# MonsterMoto-Shield-v12.net
KiCad netlist of a schematic drawn in EAGLE
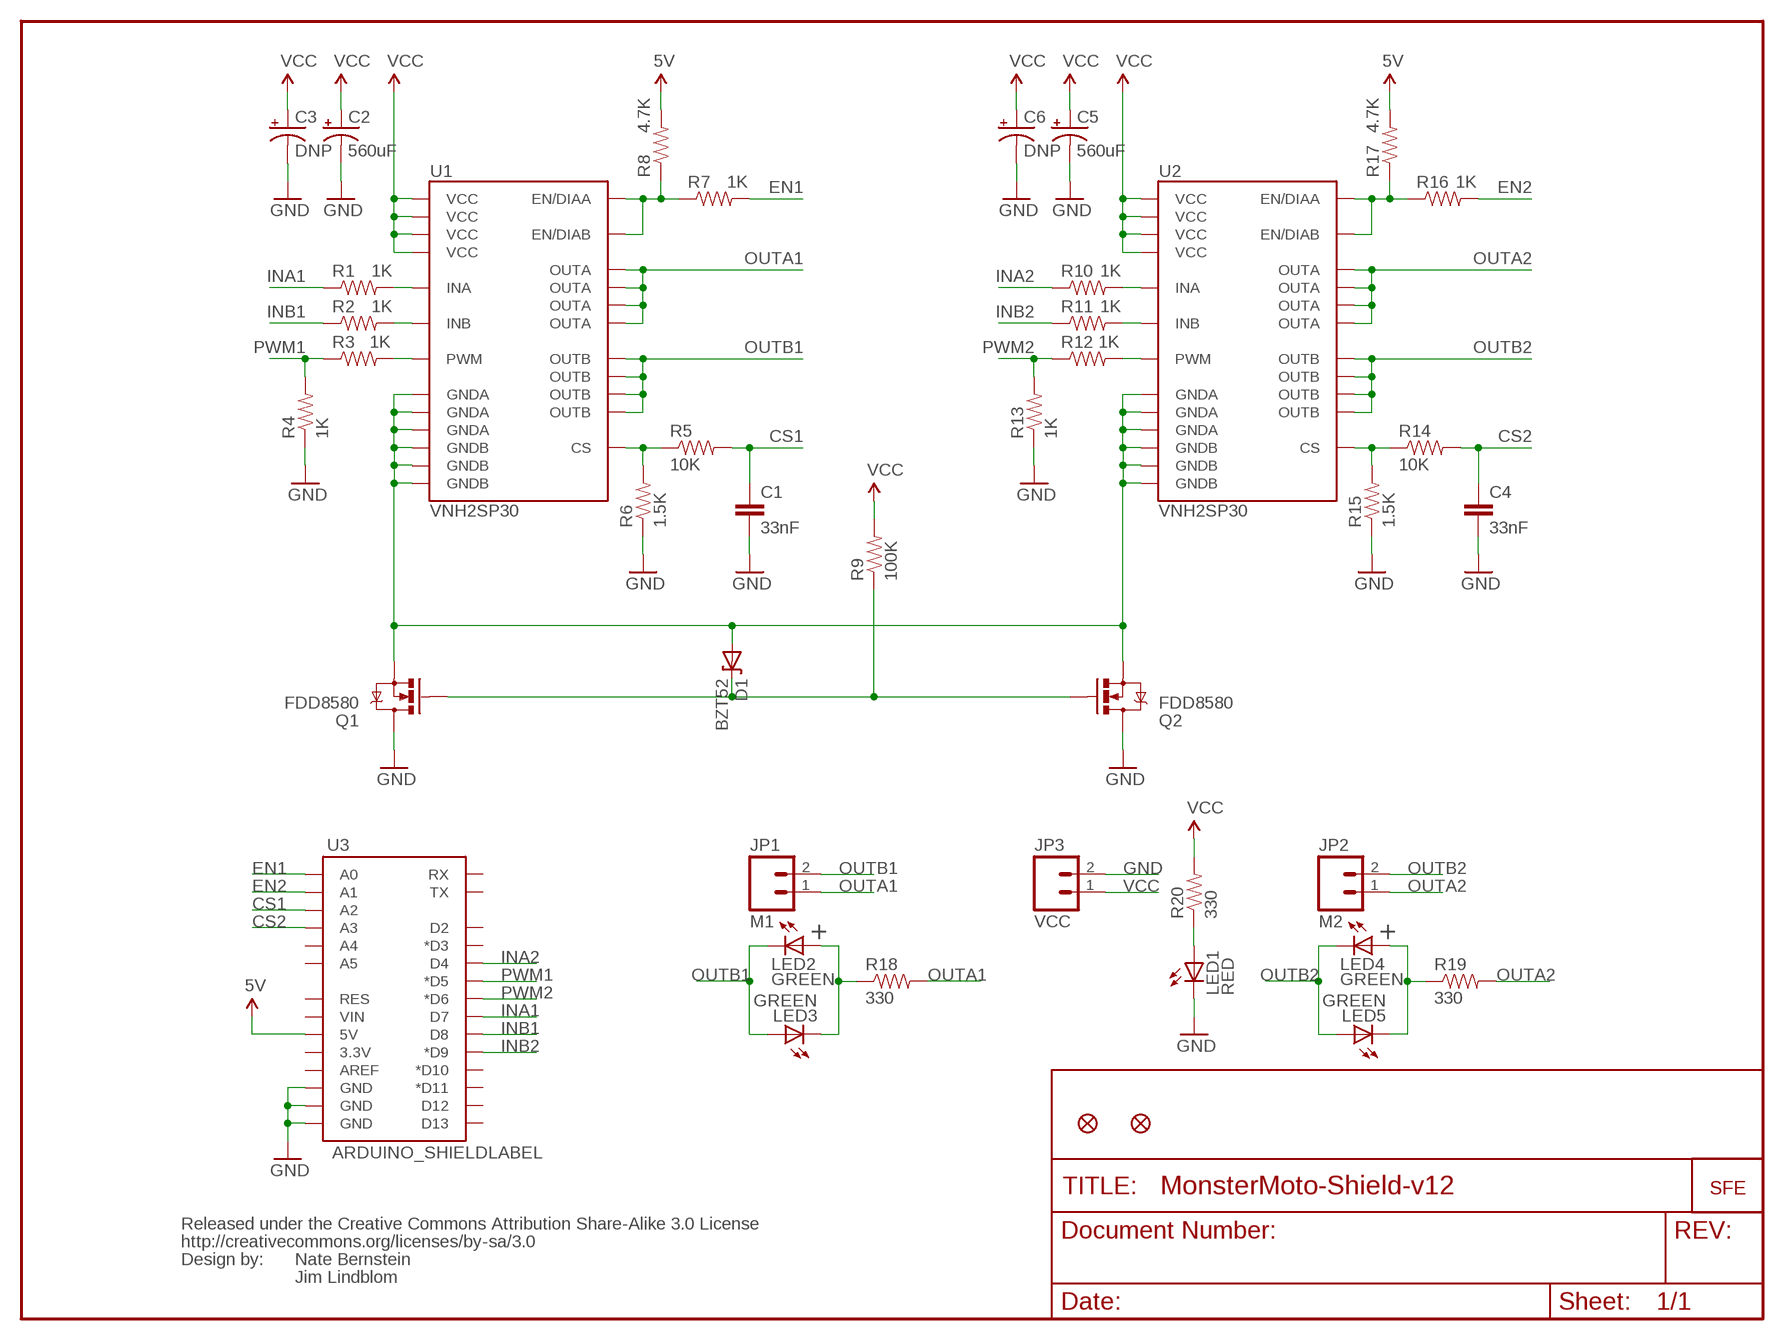
[diagram p0: schematic, sheet 1]

(export (version "E")
  (design (tool "Eeschema 10.0.6"))
  (components
    (comp (ref "C1")
      (value "33nF")
      (footprint "eagle-import:0402-CAP")
      (libsource (lib "eagle-import") (part "CAP0402-CAP"))
    )
    (comp (ref "C2")
      (value "560uF")
      (footprint "eagle-import:PANASONIC_G")
      (libsource (lib "eagle-import") (part "CAP_POLG"))
    )
    (comp (ref "C3")
      (value "DNP")
      (footprint "eagle-import:CPOL-RADIAL-1000UF-25V")
      (libsource (lib "eagle-import") (part "CAP_POLPTH4"))
    )
    (comp (ref "C4")
      (value "33nF")
      (footprint "eagle-import:0402-CAP")
      (libsource (lib "eagle-import") (part "CAP0402-CAP"))
    )
    (comp (ref "C5")
      (value "560uF")
      (footprint "eagle-import:PANASONIC_G")
      (libsource (lib "eagle-import") (part "CAP_POLG"))
    )
    (comp (ref "C6")
      (value "DNP")
      (footprint "eagle-import:CPOL-RADIAL-1000UF-25V")
      (libsource (lib "eagle-import") (part "CAP_POLPTH4"))
    )
    (comp (ref "D1")
      (value "BZT52")
      (footprint "eagle-import:SOD-323")
      (libsource (lib "eagle-import") (part "DIODE-ZENER-BZT52"))
    )
    (comp (ref "JP1")
      (value "M1")
      (footprint "eagle-import:1X02_XTRA_BIG")
      (libsource (lib "eagle-import") (part "M02PTH4"))
    )
    (comp (ref "JP2")
      (value "M2")
      (footprint "eagle-import:1X02_XTRA_BIG")
      (libsource (lib "eagle-import") (part "M02PTH4"))
    )
    (comp (ref "JP3")
      (value "VCC")
      (footprint "eagle-import:1X02_XTRA_BIG")
      (libsource (lib "eagle-import") (part "M02PTH4"))
    )
    (comp (ref "JP4")
      (value "FIDUCIAL1X2")
      (footprint "eagle-import:FIDUCIAL-1X2")
      (libsource (lib "eagle-import") (part "FIDUCIAL1X2"))
    )
    (comp (ref "JP5")
      (value "LOGO-SFENEW")
      (footprint "eagle-import:SFE-NEW-WEBLOGO")
      (libsource (lib "eagle-import") (part "LOGO-SFENEW"))
    )
    (comp (ref "JP6")
      (value "FIDUCIAL1X2")
      (footprint "eagle-import:FIDUCIAL-1X2")
      (libsource (lib "eagle-import") (part "FIDUCIAL1X2"))
    )
    (comp (ref "LED1")
      (value "RED")
      (footprint "eagle-import:LED-0603")
      (libsource (lib "eagle-import") (part "LED0603"))
    )
    (comp (ref "LED2")
      (value "GREEN")
      (footprint "eagle-import:LED-0603")
      (libsource (lib "eagle-import") (part "LED0603"))
    )
    (comp (ref "LED3")
      (value "GREEN")
      (footprint "eagle-import:LED-0603")
      (libsource (lib "eagle-import") (part "LED0603"))
    )
    (comp (ref "LED4")
      (value "GREEN")
      (footprint "eagle-import:LED-0603")
      (libsource (lib "eagle-import") (part "LED0603"))
    )
    (comp (ref "LED5")
      (value "GREEN")
      (footprint "eagle-import:LED-0603")
      (libsource (lib "eagle-import") (part "LED0603"))
    )
    (comp (ref "Q1")
      (value "FDD8580")
      (footprint "eagle-import:DPAK")
      (libsource (lib "eagle-import") (part "MOSFET-NCHANNELFDD8580"))
    )
    (comp (ref "Q2")
      (value "FDD8580")
      (footprint "eagle-import:DPAK")
      (libsource (lib "eagle-import") (part "MOSFET-NCHANNELFDD8580"))
    )
    (comp (ref "R1")
      (value "1K")
      (footprint "eagle-import:0402-RES")
      (libsource (lib "eagle-import") (part "RESISTOR0402-RES"))
    )
    (comp (ref "R2")
      (value "1K")
      (footprint "eagle-import:0402-RES")
      (libsource (lib "eagle-import") (part "RESISTOR0402-RES"))
    )
    (comp (ref "R3")
      (value "1K")
      (footprint "eagle-import:0402-RES")
      (libsource (lib "eagle-import") (part "RESISTOR0402-RES"))
    )
    (comp (ref "R4")
      (value "1K")
      (footprint "eagle-import:0402-RES")
      (libsource (lib "eagle-import") (part "RESISTOR0402-RES"))
    )
    (comp (ref "R5")
      (value "10K")
      (footprint "eagle-import:0402-RES")
      (libsource (lib "eagle-import") (part "RESISTOR0402-RES"))
    )
    (comp (ref "R6")
      (value "1.5K")
      (footprint "eagle-import:0402-RES")
      (libsource (lib "eagle-import") (part "RESISTOR0402-RES"))
    )
    (comp (ref "R7")
      (value "1K")
      (footprint "eagle-import:0402-RES")
      (libsource (lib "eagle-import") (part "RESISTOR0402-RES"))
    )
    (comp (ref "R8")
      (value "4.7K")
      (footprint "eagle-import:0402-RES")
      (libsource (lib "eagle-import") (part "RESISTOR0402-RES"))
    )
    (comp (ref "R9")
      (value "100K")
      (footprint "eagle-import:0402-RES")
      (libsource (lib "eagle-import") (part "RESISTOR0402-RES"))
    )
    (comp (ref "R10")
      (value "1K")
      (footprint "eagle-import:0402-RES")
      (libsource (lib "eagle-import") (part "RESISTOR0402-RES"))
    )
    (comp (ref "R11")
      (value "1K")
      (footprint "eagle-import:0402-RES")
      (libsource (lib "eagle-import") (part "RESISTOR0402-RES"))
    )
    (comp (ref "R12")
      (value "1K")
      (footprint "eagle-import:0402-RES")
      (libsource (lib "eagle-import") (part "RESISTOR0402-RES"))
    )
    (comp (ref "R13")
      (value "1K")
      (footprint "eagle-import:0402-RES")
      (libsource (lib "eagle-import") (part "RESISTOR0402-RES"))
    )
    (comp (ref "R14")
      (value "10K")
      (footprint "eagle-import:0402-RES")
      (libsource (lib "eagle-import") (part "RESISTOR0402-RES"))
    )
    (comp (ref "R15")
      (value "1.5K")
      (footprint "eagle-import:0402-RES")
      (libsource (lib "eagle-import") (part "RESISTOR0402-RES"))
    )
    (comp (ref "R16")
      (value "1K")
      (footprint "eagle-import:0402-RES")
      (libsource (lib "eagle-import") (part "RESISTOR0402-RES"))
    )
    (comp (ref "R17")
      (value "4.7K")
      (footprint "eagle-import:0402-RES")
      (libsource (lib "eagle-import") (part "RESISTOR0402-RES"))
    )
    (comp (ref "R18")
      (value "330")
      (footprint "eagle-import:0402-RES")
      (libsource (lib "eagle-import") (part "RESISTOR0402-RES"))
    )
    (comp (ref "R19")
      (value "330")
      (footprint "eagle-import:0402-RES")
      (libsource (lib "eagle-import") (part "RESISTOR0402-RES"))
    )
    (comp (ref "R20")
      (value "330")
      (footprint "eagle-import:0402-RES")
      (libsource (lib "eagle-import") (part "RESISTOR0402-RES"))
    )
    (comp (ref "U$6")
      (value "CREATIVE_COMMONS")
      (footprint "eagle-import:CREATIVE_COMMONS")
      (libsource (lib "eagle-import") (part "CREATIVE_COMMONS"))
    )
    (comp (ref "U1")
      (value "VNH2SP30")
      (footprint "eagle-import:VNH2SP30")
      (libsource (lib "eagle-import") (part "VNH2SP30"))
    )
    (comp (ref "U2")
      (value "VNH2SP30")
      (footprint "eagle-import:VNH2SP30")
      (libsource (lib "eagle-import") (part "VNH2SP30"))
    )
    (comp (ref "U3")
      (value "ARDUINO_SHIELDLABEL")
      (footprint "eagle-import:DUEMILANOVE_SHIELD")
      (libsource (lib "eagle-import") (part "ARDUINO_SHIELDLABEL"))
    )
  )
  (nets
    (net (code "1") (name "/CS1") (class "Default")
      (node (ref "C1") (pin "1") (pinfunction "1_1") (pintype "passive"))
      (node (ref "R5") (pin "2") (pinfunction "2_2") (pintype "passive"))
      (node (ref "U3") (pin "A2") (pinfunction "A2_A2") (pintype "bidirectional"))
    )
    (net (code "2") (name "/CS2") (class "Default")
      (node (ref "C4") (pin "1") (pinfunction "1_1") (pintype "passive"))
      (node (ref "R14") (pin "2") (pinfunction "2_2") (pintype "passive"))
      (node (ref "U3") (pin "A3") (pinfunction "A3_A3") (pintype "bidirectional"))
    )
    (net (code "3") (name "/EN1") (class "Default")
      (node (ref "R7") (pin "2") (pinfunction "2_2") (pintype "passive"))
      (node (ref "U3") (pin "A0") (pinfunction "A0_A0") (pintype "bidirectional"))
    )
    (net (code "4") (name "/EN2") (class "Default")
      (node (ref "R16") (pin "2") (pinfunction "2_2") (pintype "passive"))
      (node (ref "U3") (pin "A1") (pinfunction "A1_A1") (pintype "bidirectional"))
    )
    (net (code "5") (name "/INA1") (class "Default")
      (node (ref "R1") (pin "1") (pinfunction "1_1") (pintype "passive"))
      (node (ref "U3") (pin "D7") (pinfunction "D7_D7") (pintype "bidirectional"))
    )
    (net (code "6") (name "/INA2") (class "Default")
      (node (ref "R10") (pin "1") (pinfunction "1_1") (pintype "passive"))
      (node (ref "U3") (pin "D4") (pinfunction "D4_D4") (pintype "bidirectional"))
    )
    (net (code "7") (name "/INB1") (class "Default")
      (node (ref "R2") (pin "1") (pinfunction "1_1") (pintype "passive"))
      (node (ref "U3") (pin "D8") (pinfunction "D8_D8") (pintype "bidirectional"))
    )
    (net (code "8") (name "/INB2") (class "Default")
      (node (ref "R11") (pin "1") (pinfunction "1_1") (pintype "passive"))
      (node (ref "U3") (pin "D9") (pinfunction "*D9_D9") (pintype "bidirectional"))
    )
    (net (code "9") (name "/OUTA1") (class "Default")
      (node (ref "JP1") (pin "1") (pinfunction "1_1") (pintype "passive"))
      (node (ref "R18") (pin "2") (pinfunction "2_2") (pintype "passive"))
      (node (ref "U1") (pin "1") (pinfunction "OUTA_1") (pintype "bidirectional"))
      (node (ref "U1") (pin "25") (pinfunction "OUTA_25") (pintype "bidirectional"))
      (node (ref "U1") (pin "30") (pinfunction "OUTA_30") (pintype "bidirectional"))
      (node (ref "U1") (pin "SLUG3") (pinfunction "OUTA_SLUG3") (pintype "bidirectional"))
    )
    (net (code "10") (name "/OUTA2") (class "Default")
      (node (ref "JP2") (pin "1") (pinfunction "1_1") (pintype "passive"))
      (node (ref "R19") (pin "2") (pinfunction "2_2") (pintype "passive"))
      (node (ref "U2") (pin "1") (pinfunction "OUTA_1") (pintype "bidirectional"))
      (node (ref "U2") (pin "25") (pinfunction "OUTA_25") (pintype "bidirectional"))
      (node (ref "U2") (pin "30") (pinfunction "OUTA_30") (pintype "bidirectional"))
      (node (ref "U2") (pin "SLUG3") (pinfunction "OUTA_SLUG3") (pintype "bidirectional"))
    )
    (net (code "11") (name "/OUTB1") (class "Default")
      (node (ref "JP1") (pin "2") (pinfunction "2_2") (pintype "passive"))
      (node (ref "LED2") (pin "C") (pinfunction "C_C") (pintype "passive"))
      (node (ref "LED3") (pin "A") (pinfunction "A_A") (pintype "passive"))
      (node (ref "U1") (pin "15") (pinfunction "OUTB_15") (pintype "bidirectional"))
      (node (ref "U1") (pin "16") (pinfunction "OUTB_16") (pintype "bidirectional"))
      (node (ref "U1") (pin "21") (pinfunction "OUTB_21") (pintype "bidirectional"))
      (node (ref "U1") (pin "SLUG2") (pinfunction "OUTB_SLUG2") (pintype "bidirectional"))
    )
    (net (code "12") (name "/OUTB2") (class "Default")
      (node (ref "JP2") (pin "2") (pinfunction "2_2") (pintype "passive"))
      (node (ref "LED4") (pin "C") (pinfunction "C_C") (pintype "passive"))
      (node (ref "LED5") (pin "A") (pinfunction "A_A") (pintype "passive"))
      (node (ref "U2") (pin "15") (pinfunction "OUTB_15") (pintype "bidirectional"))
      (node (ref "U2") (pin "16") (pinfunction "OUTB_16") (pintype "bidirectional"))
      (node (ref "U2") (pin "21") (pinfunction "OUTB_21") (pintype "bidirectional"))
      (node (ref "U2") (pin "SLUG2") (pinfunction "OUTB_SLUG2") (pintype "bidirectional"))
    )
    (net (code "13") (name "/PWM1") (class "Default")
      (node (ref "R3") (pin "1") (pinfunction "1_1") (pintype "passive"))
      (node (ref "R4") (pin "2") (pinfunction "2_2") (pintype "passive"))
      (node (ref "U3") (pin "D5") (pinfunction "*D5_D5") (pintype "bidirectional"))
    )
    (net (code "14") (name "/PWM2") (class "Default")
      (node (ref "R12") (pin "1") (pinfunction "1_1") (pintype "passive"))
      (node (ref "R13") (pin "2") (pinfunction "2_2") (pintype "passive"))
      (node (ref "U3") (pin "D6") (pinfunction "*D6_D6") (pintype "bidirectional"))
    )
    (net (code "15") (name "5V") (class "Default")
      (node (ref "R17") (pin "2") (pinfunction "2_2") (pintype "passive"))
      (node (ref "R8") (pin "2") (pinfunction "2_2") (pintype "passive"))
      (node (ref "U3") (pin "5V") (pinfunction "5V_5V") (pintype "bidirectional"))
    )
    (net (code "16") (name "GND") (class "Default")
      (node (ref "C1") (pin "2") (pinfunction "2_2") (pintype "passive"))
      (node (ref "C2") (pin "-") (pinfunction "-_-") (pintype "passive"))
      (node (ref "C3") (pin "2") (pinfunction "-_2") (pintype "passive"))
      (node (ref "C4") (pin "2") (pinfunction "2_2") (pintype "passive"))
      (node (ref "C5") (pin "-") (pinfunction "-_-") (pintype "passive"))
      (node (ref "C6") (pin "2") (pinfunction "-_2") (pintype "passive"))
      (node (ref "JP3") (pin "2") (pinfunction "2_2") (pintype "passive"))
      (node (ref "LED1") (pin "C") (pinfunction "C_C") (pintype "passive"))
      (node (ref "Q1") (pin "4") (pinfunction "D_4") (pintype "passive"))
      (node (ref "Q2") (pin "4") (pinfunction "D_4") (pintype "passive"))
      (node (ref "R13") (pin "1") (pinfunction "1_1") (pintype "passive"))
      (node (ref "R15") (pin "1") (pinfunction "1_1") (pintype "passive"))
      (node (ref "R4") (pin "1") (pinfunction "1_1") (pintype "passive"))
      (node (ref "R6") (pin "1") (pinfunction "1_1") (pintype "passive"))
      (node (ref "U3") (pin "GND@0") (pinfunction "GND_GND@0") (pintype "bidirectional"))
      (node (ref "U3") (pin "GND@1") (pinfunction "GND_GND@1") (pintype "bidirectional"))
      (node (ref "U3") (pin "GND@2") (pinfunction "GND_GND@2") (pintype "bidirectional"))
    )
    (net (code "17") (name "Net-(D1-A)") (class "Default")
      (node (ref "D1") (pin "2") (pinfunction "A_2") (pintype "passive"))
      (node (ref "Q1") (pin "3") (pinfunction "S_3") (pintype "passive"))
      (node (ref "Q2") (pin "3") (pinfunction "S_3") (pintype "passive"))
      (node (ref "U1") (pin "18") (pinfunction "GNDB_18") (pintype "bidirectional"))
      (node (ref "U1") (pin "19") (pinfunction "GNDB_19") (pintype "bidirectional"))
      (node (ref "U1") (pin "20") (pinfunction "GNDB_20") (pintype "bidirectional"))
      (node (ref "U1") (pin "26") (pinfunction "GNDA_26") (pintype "bidirectional"))
      (node (ref "U1") (pin "27") (pinfunction "GNDA_27") (pintype "bidirectional"))
      (node (ref "U1") (pin "28") (pinfunction "GNDA_28") (pintype "bidirectional"))
      (node (ref "U2") (pin "18") (pinfunction "GNDB_18") (pintype "bidirectional"))
      (node (ref "U2") (pin "19") (pinfunction "GNDB_19") (pintype "bidirectional"))
      (node (ref "U2") (pin "20") (pinfunction "GNDB_20") (pintype "bidirectional"))
      (node (ref "U2") (pin "26") (pinfunction "GNDA_26") (pintype "bidirectional"))
      (node (ref "U2") (pin "27") (pinfunction "GNDA_27") (pintype "bidirectional"))
      (node (ref "U2") (pin "28") (pinfunction "GNDA_28") (pintype "bidirectional"))
    )
    (net (code "18") (name "Net-(D1-C)") (class "Default")
      (node (ref "D1") (pin "1") (pinfunction "C_1") (pintype "passive"))
      (node (ref "Q1") (pin "1") (pinfunction "G_1") (pintype "passive"))
      (node (ref "Q2") (pin "1") (pinfunction "G_1") (pintype "passive"))
      (node (ref "R9") (pin "1") (pinfunction "1_1") (pintype "passive"))
    )
    (net (code "19") (name "Net-(LED1-PadA)") (class "Default")
      (node (ref "LED1") (pin "A") (pinfunction "A_A") (pintype "passive"))
      (node (ref "R20") (pin "1") (pinfunction "1_1") (pintype "passive"))
    )
    (net (code "20") (name "Net-(LED2-PadA)") (class "Default")
      (node (ref "LED2") (pin "A") (pinfunction "A_A") (pintype "passive"))
      (node (ref "LED3") (pin "C") (pinfunction "C_C") (pintype "passive"))
      (node (ref "R18") (pin "1") (pinfunction "1_1") (pintype "passive"))
    )
    (net (code "21") (name "Net-(LED4-PadA)") (class "Default")
      (node (ref "LED4") (pin "A") (pinfunction "A_A") (pintype "passive"))
      (node (ref "LED5") (pin "C") (pinfunction "C_C") (pintype "passive"))
      (node (ref "R19") (pin "1") (pinfunction "1_1") (pintype "passive"))
    )
    (net (code "22") (name "Net-(U1-CS)") (class "Default")
      (node (ref "R5") (pin "1") (pinfunction "1_1") (pintype "passive"))
      (node (ref "R6") (pin "2") (pinfunction "2_2") (pintype "passive"))
      (node (ref "U1") (pin "9") (pinfunction "CS_9") (pintype "bidirectional"))
    )
    (net (code "23") (name "Net-(U1-EN{slash}DIAA)") (class "Default")
      (node (ref "R7") (pin "1") (pinfunction "1_1") (pintype "passive"))
      (node (ref "R8") (pin "1") (pinfunction "1_1") (pintype "passive"))
      (node (ref "U1") (pin "10") (pinfunction "EN/DIAB_10") (pintype "bidirectional"))
      (node (ref "U1") (pin "6") (pinfunction "EN/DIAA_6") (pintype "bidirectional"))
    )
    (net (code "24") (name "Net-(U1-INA)") (class "Default")
      (node (ref "R1") (pin "2") (pinfunction "2_2") (pintype "passive"))
      (node (ref "U1") (pin "5") (pinfunction "INA_5") (pintype "bidirectional"))
    )
    (net (code "25") (name "Net-(U1-INB)") (class "Default")
      (node (ref "R2") (pin "2") (pinfunction "2_2") (pintype "passive"))
      (node (ref "U1") (pin "11") (pinfunction "INB_11") (pintype "bidirectional"))
    )
    (net (code "26") (name "Net-(U1-PWM)") (class "Default")
      (node (ref "R3") (pin "2") (pinfunction "2_2") (pintype "passive"))
      (node (ref "U1") (pin "8") (pinfunction "PWM_8") (pintype "bidirectional"))
    )
    (net (code "27") (name "Net-(U2-CS)") (class "Default")
      (node (ref "R14") (pin "1") (pinfunction "1_1") (pintype "passive"))
      (node (ref "R15") (pin "2") (pinfunction "2_2") (pintype "passive"))
      (node (ref "U2") (pin "9") (pinfunction "CS_9") (pintype "bidirectional"))
    )
    (net (code "28") (name "Net-(U2-EN{slash}DIAA)") (class "Default")
      (node (ref "R16") (pin "1") (pinfunction "1_1") (pintype "passive"))
      (node (ref "R17") (pin "1") (pinfunction "1_1") (pintype "passive"))
      (node (ref "U2") (pin "10") (pinfunction "EN/DIAB_10") (pintype "bidirectional"))
      (node (ref "U2") (pin "6") (pinfunction "EN/DIAA_6") (pintype "bidirectional"))
    )
    (net (code "29") (name "Net-(U2-INA)") (class "Default")
      (node (ref "R10") (pin "2") (pinfunction "2_2") (pintype "passive"))
      (node (ref "U2") (pin "5") (pinfunction "INA_5") (pintype "bidirectional"))
    )
    (net (code "30") (name "Net-(U2-INB)") (class "Default")
      (node (ref "R11") (pin "2") (pinfunction "2_2") (pintype "passive"))
      (node (ref "U2") (pin "11") (pinfunction "INB_11") (pintype "bidirectional"))
    )
    (net (code "31") (name "Net-(U2-PWM)") (class "Default")
      (node (ref "R12") (pin "2") (pinfunction "2_2") (pintype "passive"))
      (node (ref "U2") (pin "8") (pinfunction "PWM_8") (pintype "bidirectional"))
    )
    (net (code "32") (name "VCC") (class "Default")
      (node (ref "C2") (pin "+") (pinfunction "+_+") (pintype "passive"))
      (node (ref "C3") (pin "1") (pinfunction "+_1") (pintype "passive"))
      (node (ref "C5") (pin "+") (pinfunction "+_+") (pintype "passive"))
      (node (ref "C6") (pin "1") (pinfunction "+_1") (pintype "passive"))
      (node (ref "JP3") (pin "1") (pinfunction "1_1") (pintype "passive"))
      (node (ref "R20") (pin "2") (pinfunction "2_2") (pintype "passive"))
      (node (ref "R9") (pin "2") (pinfunction "2_2") (pintype "passive"))
      (node (ref "U1") (pin "13") (pinfunction "VCC_13") (pintype "bidirectional"))
      (node (ref "U1") (pin "23") (pinfunction "VCC_23") (pintype "bidirectional"))
      (node (ref "U1") (pin "3") (pinfunction "VCC_3") (pintype "bidirectional"))
      (node (ref "U1") (pin "SLUG1") (pinfunction "VCC_SLUG1") (pintype "bidirectional"))
      (node (ref "U2") (pin "13") (pinfunction "VCC_13") (pintype "bidirectional"))
      (node (ref "U2") (pin "23") (pinfunction "VCC_23") (pintype "bidirectional"))
      (node (ref "U2") (pin "3") (pinfunction "VCC_3") (pintype "bidirectional"))
      (node (ref "U2") (pin "SLUG1") (pinfunction "VCC_SLUG1") (pintype "bidirectional"))
    )
    (net (code "33") (name "unconnected-(U3-*D3-PadD3)") (class "Default")
      (node (ref "U3") (pin "D3") (pinfunction "*D3_D3") (pintype "bidirectional"))
    )
    (net (code "34") (name "unconnected-(U3-*D10-PadD10)") (class "Default")
      (node (ref "U3") (pin "D10") (pinfunction "*D10_D10") (pintype "bidirectional"))
    )
    (net (code "35") (name "unconnected-(U3-*D11-PadD11)") (class "Default")
      (node (ref "U3") (pin "D11") (pinfunction "*D11_D11") (pintype "bidirectional"))
    )
    (net (code "36") (name "unconnected-(U3-Pad3.3V)") (class "Default")
      (node (ref "U3") (pin "3.3V") (pinfunction "3.3V_3.3V") (pintype "bidirectional"))
    )
    (net (code "37") (name "unconnected-(U3-PadA4)") (class "Default")
      (node (ref "U3") (pin "A4") (pinfunction "A4_A4") (pintype "bidirectional"))
    )
    (net (code "38") (name "unconnected-(U3-PadA5)") (class "Default")
      (node (ref "U3") (pin "A5") (pinfunction "A5_A5") (pintype "bidirectional"))
    )
    (net (code "39") (name "unconnected-(U3-PadAREF)") (class "Default")
      (node (ref "U3") (pin "AREF") (pinfunction "AREF_AREF") (pintype "bidirectional"))
    )
    (net (code "40") (name "unconnected-(U3-PadD2)") (class "Default")
      (node (ref "U3") (pin "D2") (pinfunction "D2_D2") (pintype "bidirectional"))
    )
    (net (code "41") (name "unconnected-(U3-PadD12)") (class "Default")
      (node (ref "U3") (pin "D12") (pinfunction "D12_D12") (pintype "bidirectional"))
    )
    (net (code "42") (name "unconnected-(U3-PadD13)") (class "Default")
      (node (ref "U3") (pin "D13") (pinfunction "D13_D13") (pintype "bidirectional"))
    )
    (net (code "43") (name "unconnected-(U3-PadRES)") (class "Default")
      (node (ref "U3") (pin "RES") (pinfunction "RES_RES") (pintype "bidirectional"))
    )
    (net (code "44") (name "unconnected-(U3-PadRX)") (class "Default")
      (node (ref "U3") (pin "RX") (pinfunction "RX_RX") (pintype "bidirectional"))
    )
    (net (code "45") (name "unconnected-(U3-PadTX)") (class "Default")
      (node (ref "U3") (pin "TX") (pinfunction "TX_TX") (pintype "bidirectional"))
    )
    (net (code "46") (name "unconnected-(U3-PadVIN)") (class "Default")
      (node (ref "U3") (pin "VIN") (pinfunction "VIN_VIN") (pintype "bidirectional"))
    )
  )
)
